# Carolo_20200123.net
KiCad netlist of a schematic drawn in EAGLE
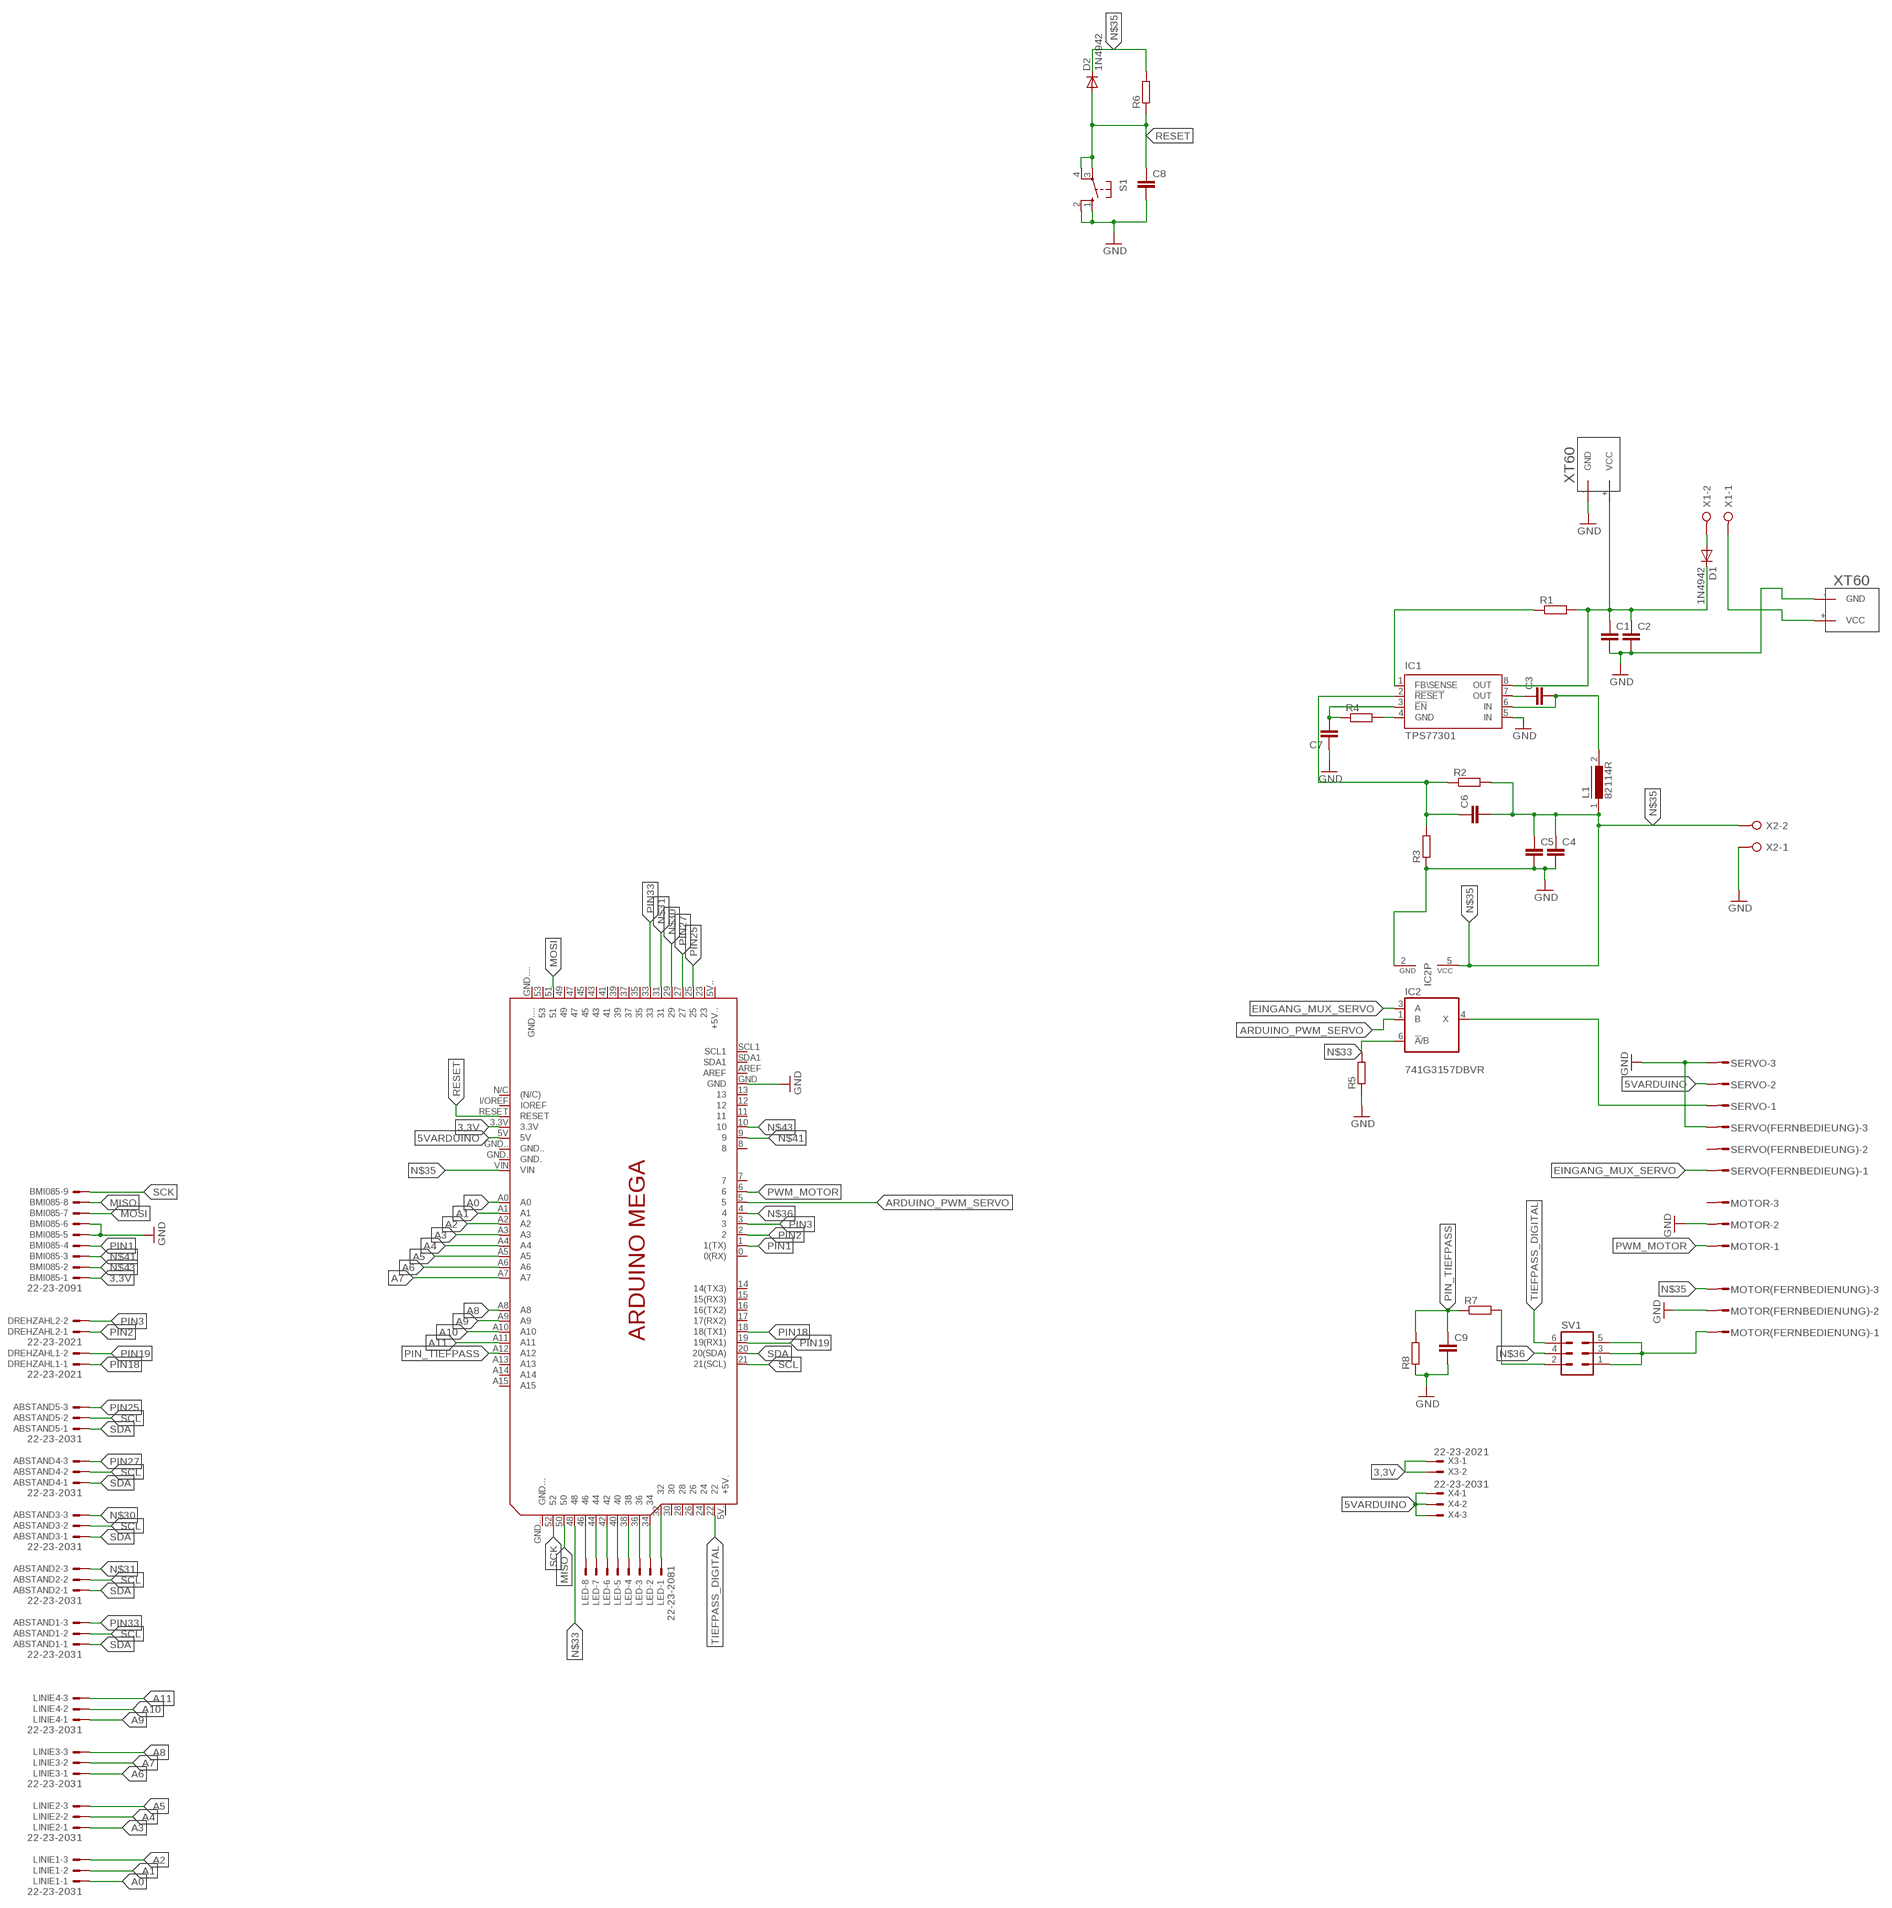
[diagram p0: schematic, sheet 1]

(export (version "E")
  (design (tool "Eeschema 10.0.6"))
  (components
    (comp (ref "ABSTAND1")
      (value "22-23-2031")
      (footprint "eagle-import:22-23-2031")
      (fields (field (name "MF") "MOLEX"))
      (libsource (lib "eagle-import") (part "22-23-2031"))
    )
    (comp (ref "ABSTAND2")
      (value "22-23-2031")
      (footprint "eagle-import:22-23-2031")
      (fields (field (name "MF") "MOLEX"))
      (libsource (lib "eagle-import") (part "22-23-2031"))
    )
    (comp (ref "ABSTAND3")
      (value "22-23-2031")
      (footprint "eagle-import:22-23-2031")
      (fields (field (name "MF") "MOLEX"))
      (libsource (lib "eagle-import") (part "22-23-2031"))
    )
    (comp (ref "ABSTAND4")
      (value "22-23-2031")
      (footprint "eagle-import:22-23-2031")
      (fields (field (name "MF") "MOLEX"))
      (libsource (lib "eagle-import") (part "22-23-2031"))
    )
    (comp (ref "ABSTAND5")
      (value "22-23-2031")
      (footprint "eagle-import:22-23-2031")
      (fields (field (name "MF") "MOLEX"))
      (libsource (lib "eagle-import") (part "22-23-2031"))
    )
    (comp (ref "BMI085")
      (value "22-23-2091")
      (footprint "eagle-import:22-23-2091")
      (fields (field (name "MF") "MOLEX"))
      (libsource (lib "eagle-import") (part "22-23-2091"))
    )
    (comp (ref "C1")
      (value "C2,5-3")
      (footprint "eagle-import:C2.5-3")
      (libsource (lib "eagle-import") (part "C2,5-3"))
    )
    (comp (ref "C2")
      (value "C2,5-3")
      (footprint "eagle-import:C2.5-3")
      (libsource (lib "eagle-import") (part "C2,5-3"))
    )
    (comp (ref "C3")
      (value "C2,5-3")
      (footprint "eagle-import:C2.5-3")
      (libsource (lib "eagle-import") (part "C2,5-3"))
    )
    (comp (ref "C4")
      (value "C2,5-3")
      (footprint "eagle-import:C2.5-3")
      (libsource (lib "eagle-import") (part "C2,5-3"))
    )
    (comp (ref "C5")
      (value "C2,5-3")
      (footprint "eagle-import:C2.5-3")
      (libsource (lib "eagle-import") (part "C2,5-3"))
    )
    (comp (ref "C6")
      (value "C2,5-3")
      (footprint "eagle-import:C2.5-3")
      (libsource (lib "eagle-import") (part "C2,5-3"))
    )
    (comp (ref "C7")
      (value "C2,5-3")
      (footprint "eagle-import:C2.5-3")
      (libsource (lib "eagle-import") (part "C2,5-3"))
    )
    (comp (ref "C8")
      (value "C2,5-3")
      (footprint "eagle-import:C2.5-3")
      (libsource (lib "eagle-import") (part "C2,5-3"))
    )
    (comp (ref "C9")
      (value "C2,5-3")
      (footprint "eagle-import:C2.5-3")
      (libsource (lib "eagle-import") (part "C2,5-3"))
    )
    (comp (ref "D1")
      (value "1N4942")
      (footprint "eagle-import:DO41-10")
      (libsource (lib "eagle-import") (part "1N4942"))
    )
    (comp (ref "D2")
      (value "1N4942")
      (footprint "eagle-import:DO41-10")
      (libsource (lib "eagle-import") (part "1N4942"))
    )
    (comp (ref "DREHZAHL1")
      (value "22-23-2021")
      (footprint "eagle-import:22-23-2021")
      (fields (field (name "MF") "MOLEX"))
      (libsource (lib "eagle-import") (part "22-23-2021"))
    )
    (comp (ref "DREHZAHL2")
      (value "22-23-2021")
      (footprint "eagle-import:22-23-2021")
      (fields (field (name "MF") "MOLEX"))
      (libsource (lib "eagle-import") (part "22-23-2021"))
    )
    (comp (ref "IC1")
      (value "TPS77301")
      (footprint "eagle-import:SOP-08")
      (fields (field (name "MF") "TEXAS INSTRUMENT CONNECTORS") (field (name "MPN") "TPS77301DGK"))
      (libsource (lib "eagle-import") (part "TPS77301"))
    )
    (comp (ref "IC2")
      (value "741G3157DBVR")
      (footprint "eagle-import:DBV_R-PDSO-G6")
      (libsource (lib "eagle-import") (part "741G3157DBVR"))
    )
    (comp (ref "L1")
      (value "82114R")
      (footprint "eagle-import:82114R")
      (libsource (lib "eagle-import") (part "82114R"))
    )
    (comp (ref "LED")
      (value "22-23-2081")
      (footprint "eagle-import:22-23-2081")
      (fields (field (name "MF") "MOLEX"))
      (libsource (lib "eagle-import") (part "22-23-2081"))
    )
    (comp (ref "LINIE1")
      (value "22-23-2031")
      (footprint "eagle-import:22-23-2031")
      (fields (field (name "MF") "MOLEX"))
      (libsource (lib "eagle-import") (part "22-23-2031"))
    )
    (comp (ref "LINIE2")
      (value "22-23-2031")
      (footprint "eagle-import:22-23-2031")
      (fields (field (name "MF") "MOLEX"))
      (libsource (lib "eagle-import") (part "22-23-2031"))
    )
    (comp (ref "LINIE3")
      (value "22-23-2031")
      (footprint "eagle-import:22-23-2031")
      (fields (field (name "MF") "MOLEX"))
      (libsource (lib "eagle-import") (part "22-23-2031"))
    )
    (comp (ref "LINIE4")
      (value "22-23-2031")
      (footprint "eagle-import:22-23-2031")
      (fields (field (name "MF") "MOLEX"))
      (libsource (lib "eagle-import") (part "22-23-2031"))
    )
    (comp (ref "MOTOR")
      (value "L03P")
      (footprint "eagle-import:L03P")
      (libsource (lib "eagle-import") (part "L03P"))
    )
    (comp (ref "MOTOR(FERNBEDIENUNG)")
      (value "L03P")
      (footprint "eagle-import:L03P")
      (libsource (lib "eagle-import") (part "L03P"))
    )
    (comp (ref "PCB1")
      (value "ARDUINO_MEGA")
      (footprint "eagle-import:ARDUINO_MEGA")
      (libsource (lib "eagle-import") (part "ARDUINO_MEGA"))
    )
    (comp (ref "R1")
      (value "R-EU_0411/15")
      (footprint "eagle-import:0411_15")
      (libsource (lib "eagle-import") (part "R-EU_0411/15"))
    )
    (comp (ref "R2")
      (value "R-EU_0411/15")
      (footprint "eagle-import:0411_15")
      (libsource (lib "eagle-import") (part "R-EU_0411/15"))
    )
    (comp (ref "R3")
      (value "R-EU_0411/15")
      (footprint "eagle-import:0411_15")
      (libsource (lib "eagle-import") (part "R-EU_0411/15"))
    )
    (comp (ref "R4")
      (value "R-EU_0411/15")
      (footprint "eagle-import:0411_15")
      (libsource (lib "eagle-import") (part "R-EU_0411/15"))
    )
    (comp (ref "R5")
      (value "R-EU_0411/15")
      (footprint "eagle-import:0411_15")
      (libsource (lib "eagle-import") (part "R-EU_0411/15"))
    )
    (comp (ref "R6")
      (value "R-EU_0411/15")
      (footprint "eagle-import:0411_15")
      (libsource (lib "eagle-import") (part "R-EU_0411/15"))
    )
    (comp (ref "R7")
      (value "R-EU_0411/15")
      (footprint "eagle-import:0411_15")
      (libsource (lib "eagle-import") (part "R-EU_0411/15"))
    )
    (comp (ref "R8")
      (value "R-EU_0411/15")
      (footprint "eagle-import:0411_15")
      (libsource (lib "eagle-import") (part "R-EU_0411/15"))
    )
    (comp (ref "S1")
      (value "10-XX")
      (footprint "eagle-import:B3F-10XX")
      (fields (field (name "MPN") "B3F-1000"))
      (libsource (lib "eagle-import") (part "10-XX"))
    )
    (comp (ref "SERVO")
      (value "L03P")
      (footprint "eagle-import:L03P")
      (libsource (lib "eagle-import") (part "L03P"))
    )
    (comp (ref "SERVO(FERNBEDIEUNG)")
      (value "L03P")
      (footprint "eagle-import:L03P")
      (libsource (lib "eagle-import") (part "L03P"))
    )
    (comp (ref "SV1")
      (value "ML6")
      (footprint "eagle-import:ML6")
      (libsource (lib "eagle-import") (part "ML6"))
    )
    (comp (ref "U$1")
      (value "XT60")
      (footprint "eagle-import:XT60")
      (libsource (lib "eagle-import") (part "XT60"))
    )
    (comp (ref "U$2")
      (value "XT60")
      (footprint "eagle-import:XT60")
      (libsource (lib "eagle-import") (part "XT60"))
    )
    (comp (ref "X1")
      (value "W237-02P")
      (footprint "eagle-import:W237-132")
      (libsource (lib "eagle-import") (part "W237-02P"))
    )
    (comp (ref "X2")
      (value "W237-02P")
      (footprint "eagle-import:W237-132")
      (libsource (lib "eagle-import") (part "W237-02P"))
    )
    (comp (ref "X3")
      (value "22-23-2021")
      (footprint "eagle-import:22-23-2021")
      (fields (field (name "MF") "MOLEX"))
      (libsource (lib "eagle-import") (part "22-23-2021"))
    )
    (comp (ref "X4")
      (value "22-23-2031")
      (footprint "eagle-import:22-23-2031")
      (fields (field (name "MF") "MOLEX"))
      (libsource (lib "eagle-import") (part "22-23-2031"))
    )
  )
  (nets
    (net (code "1") (name "3,3V") (class "Default")
      (node (ref "BMI085") (pin "1") (pinfunction "S_1") (pintype "passive"))
      (node (ref "PCB1") (pin "3.3V") (pinfunction "3.3V_3.3V") (pintype "bidirectional"))
      (node (ref "X3") (pin "1") (pinfunction "S_1") (pintype "passive"))
      (node (ref "X3") (pin "2") (pinfunction "S_2") (pintype "passive"))
    )
    (net (code "2") (name "5VARDUINO") (class "Default")
      (node (ref "PCB1") (pin "5V") (pinfunction "5V_5V") (pintype "bidirectional"))
      (node (ref "SERVO") (pin "2") (pinfunction "S_2") (pintype "passive"))
      (node (ref "X4") (pin "1") (pinfunction "S_1") (pintype "passive"))
      (node (ref "X4") (pin "2") (pinfunction "S_2") (pintype "passive"))
      (node (ref "X4") (pin "3") (pinfunction "S_3") (pintype "passive"))
    )
    (net (code "3") (name "A0") (class "Default")
      (node (ref "LINIE1") (pin "1") (pinfunction "S_1") (pintype "passive"))
      (node (ref "PCB1") (pin "A0") (pinfunction "A0_A0") (pintype "bidirectional"))
    )
    (net (code "4") (name "A1") (class "Default")
      (node (ref "LINIE1") (pin "2") (pinfunction "S_2") (pintype "passive"))
      (node (ref "PCB1") (pin "A1") (pinfunction "A1_A1") (pintype "bidirectional"))
    )
    (net (code "5") (name "A2") (class "Default")
      (node (ref "LINIE1") (pin "3") (pinfunction "S_3") (pintype "passive"))
      (node (ref "PCB1") (pin "A2") (pinfunction "A2_A2") (pintype "bidirectional"))
    )
    (net (code "6") (name "A3") (class "Default")
      (node (ref "LINIE2") (pin "1") (pinfunction "S_1") (pintype "passive"))
      (node (ref "PCB1") (pin "A3") (pinfunction "A3_A3") (pintype "bidirectional"))
    )
    (net (code "7") (name "A4") (class "Default")
      (node (ref "LINIE2") (pin "2") (pinfunction "S_2") (pintype "passive"))
      (node (ref "PCB1") (pin "A4") (pinfunction "A4_A4") (pintype "bidirectional"))
    )
    (net (code "8") (name "A5") (class "Default")
      (node (ref "LINIE2") (pin "3") (pinfunction "S_3") (pintype "passive"))
      (node (ref "PCB1") (pin "A5") (pinfunction "A5_A5") (pintype "bidirectional"))
    )
    (net (code "9") (name "A6") (class "Default")
      (node (ref "LINIE3") (pin "1") (pinfunction "S_1") (pintype "passive"))
      (node (ref "PCB1") (pin "A6") (pinfunction "A6_A6") (pintype "bidirectional"))
    )
    (net (code "10") (name "A7") (class "Default")
      (node (ref "LINIE3") (pin "2") (pinfunction "S_2") (pintype "passive"))
      (node (ref "PCB1") (pin "A7") (pinfunction "A7_A7") (pintype "bidirectional"))
    )
    (net (code "11") (name "A8") (class "Default")
      (node (ref "LINIE3") (pin "3") (pinfunction "S_3") (pintype "passive"))
      (node (ref "PCB1") (pin "A8") (pinfunction "A8_A8") (pintype "bidirectional"))
    )
    (net (code "12") (name "A9") (class "Default")
      (node (ref "LINIE4") (pin "1") (pinfunction "S_1") (pintype "passive"))
      (node (ref "PCB1") (pin "A9") (pinfunction "A9_A9") (pintype "bidirectional"))
    )
    (net (code "13") (name "A10") (class "Default")
      (node (ref "LINIE4") (pin "2") (pinfunction "S_2") (pintype "passive"))
      (node (ref "PCB1") (pin "A10") (pinfunction "A10_A10") (pintype "bidirectional"))
    )
    (net (code "14") (name "A11") (class "Default")
      (node (ref "LINIE4") (pin "3") (pinfunction "S_3") (pintype "passive"))
      (node (ref "PCB1") (pin "A11") (pinfunction "A11_A11") (pintype "bidirectional"))
    )
    (net (code "15") (name "ARDUINO_PWM_SERVO") (class "Default")
      (node (ref "IC2") (pin "1") (pinfunction "B_1") (pintype "bidirectional"))
      (node (ref "PCB1") (pin "5") (pinfunction "5_5") (pintype "bidirectional"))
    )
    (net (code "16") (name "EINGANG_MUX_SERVO") (class "Default")
      (node (ref "IC2") (pin "3") (pinfunction "A_3") (pintype "bidirectional"))
      (node (ref "SERVO(FERNBEDIEUNG)") (pin "1") (pinfunction "S_1") (pintype "passive"))
    )
    (net (code "17") (name "GND") (class "Default")
      (node (ref "BMI085") (pin "5") (pinfunction "S_5") (pintype "passive"))
      (node (ref "BMI085") (pin "6") (pinfunction "S_6") (pintype "passive"))
      (node (ref "C1") (pin "2") (pinfunction "2_2") (pintype "passive"))
      (node (ref "C2") (pin "2") (pinfunction "2_2") (pintype "passive"))
      (node (ref "C4") (pin "2") (pinfunction "2_2") (pintype "passive"))
      (node (ref "C5") (pin "2") (pinfunction "2_2") (pintype "passive"))
      (node (ref "C7") (pin "1") (pinfunction "1_1") (pintype "passive"))
      (node (ref "C8") (pin "2") (pinfunction "2_2") (pintype "passive"))
      (node (ref "C9") (pin "2") (pinfunction "2_2") (pintype "passive"))
      (node (ref "IC1") (pin "5") (pinfunction "IN_5") (pintype "input"))
      (node (ref "IC2") (pin "2") (pinfunction "GND_2") (pintype "power_in"))
      (node (ref "MOTOR") (pin "2") (pinfunction "S_2") (pintype "passive"))
      (node (ref "MOTOR(FERNBEDIENUNG)") (pin "2") (pinfunction "S_2") (pintype "passive"))
      (node (ref "PCB1") (pin "GND") (pinfunction "GND_GND") (pintype "bidirectional"))
      (node (ref "R3") (pin "1") (pinfunction "1_1") (pintype "passive"))
      (node (ref "R5") (pin "1") (pinfunction "1_1") (pintype "passive"))
      (node (ref "R8") (pin "1") (pinfunction "1_1") (pintype "passive"))
      (node (ref "S1") (pin "1") (pinfunction "S_1") (pintype "passive"))
      (node (ref "S1") (pin "2") (pinfunction "S1_2") (pintype "passive"))
      (node (ref "SERVO") (pin "3") (pinfunction "S_3") (pintype "passive"))
      (node (ref "SERVO(FERNBEDIEUNG)") (pin "3") (pinfunction "S_3") (pintype "passive"))
      (node (ref "U$1") (pin "-") (pinfunction "GND_-") (pintype "bidirectional"))
      (node (ref "U$2") (pin "-") (pinfunction "GND_-") (pintype "bidirectional"))
      (node (ref "X2") (pin "1") (pinfunction "KL_1") (pintype "passive"))
    )
    (net (code "18") (name "MISO") (class "Default")
      (node (ref "BMI085") (pin "8") (pinfunction "S_8") (pintype "passive"))
      (node (ref "PCB1") (pin "50") (pinfunction "50_50") (pintype "bidirectional"))
    )
    (net (code "19") (name "MOSI") (class "Default")
      (node (ref "BMI085") (pin "7") (pinfunction "S_7") (pintype "passive"))
      (node (ref "PCB1") (pin "51") (pinfunction "51_51") (pintype "bidirectional"))
    )
    (net (code "20") (name "N$30") (class "Default")
      (node (ref "ABSTAND3") (pin "3") (pinfunction "S_3") (pintype "passive"))
      (node (ref "PCB1") (pin "29") (pinfunction "29_29") (pintype "bidirectional"))
    )
    (net (code "21") (name "N$31") (class "Default")
      (node (ref "ABSTAND2") (pin "3") (pinfunction "S_3") (pintype "passive"))
      (node (ref "PCB1") (pin "31") (pinfunction "31_31") (pintype "bidirectional"))
    )
    (net (code "22") (name "N$33") (class "Default")
      (node (ref "IC2") (pin "6") (pinfunction "~{A}/B_6") (pintype "input"))
      (node (ref "PCB1") (pin "48") (pinfunction "48_48") (pintype "bidirectional"))
      (node (ref "R5") (pin "2") (pinfunction "2_2") (pintype "passive"))
    )
    (net (code "23") (name "N$35") (class "Default")
      (node (ref "C4") (pin "1") (pinfunction "1_1") (pintype "passive"))
      (node (ref "C5") (pin "1") (pinfunction "1_1") (pintype "passive"))
      (node (ref "C6") (pin "2") (pinfunction "2_2") (pintype "passive"))
      (node (ref "D2") (pin "C") (pinfunction "C_C") (pintype "passive"))
      (node (ref "IC2") (pin "5") (pinfunction "VCC_5") (pintype "power_in"))
      (node (ref "L1") (pin "1") (pinfunction "1_1") (pintype "passive"))
      (node (ref "MOTOR(FERNBEDIENUNG)") (pin "3") (pinfunction "S_3") (pintype "passive"))
      (node (ref "PCB1") (pin "VIN") (pinfunction "VIN_VIN") (pintype "bidirectional"))
      (node (ref "R2") (pin "2") (pinfunction "2_2") (pintype "passive"))
      (node (ref "R6") (pin "2") (pinfunction "2_2") (pintype "passive"))
      (node (ref "X2") (pin "2") (pinfunction "KL_2") (pintype "passive"))
    )
    (net (code "24") (name "N$36") (class "Default")
      (node (ref "PCB1") (pin "4") (pinfunction "4_4") (pintype "bidirectional"))
      (node (ref "SV1") (pin "4") (pinfunction "4_4") (pintype "passive"))
    )
    (net (code "25") (name "N$41") (class "Default")
      (node (ref "BMI085") (pin "3") (pinfunction "S_3") (pintype "passive"))
      (node (ref "PCB1") (pin "9") (pinfunction "9_9") (pintype "bidirectional"))
    )
    (net (code "26") (name "N$43") (class "Default")
      (node (ref "BMI085") (pin "2") (pinfunction "S_2") (pintype "passive"))
      (node (ref "PCB1") (pin "10") (pinfunction "10_10") (pintype "bidirectional"))
    )
    (net (code "27") (name "Net-(C3-Pad1)") (class "Default")
      (node (ref "C3") (pin "1") (pinfunction "1_1") (pintype "passive"))
      (node (ref "IC1") (pin "7") (pinfunction "OUT_7") (pintype "output"))
    )
    (net (code "28") (name "Net-(C3-Pad2)") (class "Default")
      (node (ref "C3") (pin "2") (pinfunction "2_2") (pintype "passive"))
      (node (ref "IC1") (pin "6") (pinfunction "IN_6") (pintype "input"))
      (node (ref "L1") (pin "2") (pinfunction "2_2") (pintype "passive"))
    )
    (net (code "29") (name "Net-(IC1-FB\\SENSE)") (class "Default")
      (node (ref "IC1") (pin "1") (pinfunction "FB\\SENSE_1") (pintype "input"))
      (node (ref "R1") (pin "1") (pinfunction "1_1") (pintype "passive"))
    )
    (net (code "30") (name "Net-(IC1-GND)") (class "Default")
      (node (ref "IC1") (pin "4") (pinfunction "GND_4") (pintype "power_in"))
      (node (ref "R4") (pin "2") (pinfunction "2_2") (pintype "passive"))
    )
    (net (code "31") (name "Net-(IC1-~{EN})") (class "Default")
      (node (ref "C7") (pin "2") (pinfunction "2_2") (pintype "passive"))
      (node (ref "IC1") (pin "3") (pinfunction "~{EN}_3") (pintype "input"))
      (node (ref "R4") (pin "1") (pinfunction "1_1") (pintype "passive"))
    )
    (net (code "32") (name "Net-(IC1-~{RESET})") (class "Default")
      (node (ref "C6") (pin "1") (pinfunction "1_1") (pintype "passive"))
      (node (ref "IC1") (pin "2") (pinfunction "~{RESET}_2") (pintype "input"))
      (node (ref "R2") (pin "1") (pinfunction "1_1") (pintype "passive"))
      (node (ref "R3") (pin "2") (pinfunction "2_2") (pintype "passive"))
    )
    (net (code "33") (name "Net-(IC2A-X)") (class "Default")
      (node (ref "IC2") (pin "4") (pinfunction "X_4") (pintype "bidirectional"))
      (node (ref "SERVO") (pin "1") (pinfunction "S_1") (pintype "passive"))
    )
    (net (code "34") (name "Net-(LEDA-S)") (class "Default")
      (node (ref "LED") (pin "1") (pinfunction "S_1") (pintype "passive"))
      (node (ref "PCB1") (pin "32") (pinfunction "32_32") (pintype "bidirectional"))
    )
    (net (code "35") (name "Net-(LEDB-S)") (class "Default")
      (node (ref "LED") (pin "2") (pinfunction "S_2") (pintype "passive"))
      (node (ref "PCB1") (pin "34") (pinfunction "34_34") (pintype "bidirectional"))
    )
    (net (code "36") (name "Net-(LEDC-S)") (class "Default")
      (node (ref "LED") (pin "3") (pinfunction "S_3") (pintype "passive"))
      (node (ref "PCB1") (pin "36") (pinfunction "36_36") (pintype "bidirectional"))
    )
    (net (code "37") (name "Net-(LEDD-S)") (class "Default")
      (node (ref "LED") (pin "4") (pinfunction "S_4") (pintype "passive"))
      (node (ref "PCB1") (pin "38") (pinfunction "38_38") (pintype "bidirectional"))
    )
    (net (code "38") (name "Net-(LEDE-S)") (class "Default")
      (node (ref "LED") (pin "5") (pinfunction "S_5") (pintype "passive"))
      (node (ref "PCB1") (pin "40") (pinfunction "40_40") (pintype "bidirectional"))
    )
    (net (code "39") (name "Net-(LEDF-S)") (class "Default")
      (node (ref "LED") (pin "6") (pinfunction "S_6") (pintype "passive"))
      (node (ref "PCB1") (pin "42") (pinfunction "42_42") (pintype "bidirectional"))
    )
    (net (code "40") (name "Net-(LEDG-S)") (class "Default")
      (node (ref "LED") (pin "7") (pinfunction "S_7") (pintype "passive"))
      (node (ref "PCB1") (pin "44") (pinfunction "44_44") (pintype "bidirectional"))
    )
    (net (code "41") (name "Net-(LEDH-S)") (class "Default")
      (node (ref "LED") (pin "8") (pinfunction "S_8") (pintype "passive"))
      (node (ref "PCB1") (pin "46") (pinfunction "46_46") (pintype "bidirectional"))
    )
    (net (code "42") (name "Net-(MOTOR(FERNBEDIENUNG)A-S)") (class "Default")
      (node (ref "MOTOR(FERNBEDIENUNG)") (pin "1") (pinfunction "S_1") (pintype "passive"))
      (node (ref "SV1") (pin "1") (pinfunction "1_1") (pintype "passive"))
      (node (ref "SV1") (pin "3") (pinfunction "3_3") (pintype "passive"))
      (node (ref "SV1") (pin "5") (pinfunction "5_5") (pintype "passive"))
    )
    (net (code "43") (name "Net-(R7-Pad2)") (class "Default")
      (node (ref "R7") (pin "2") (pinfunction "2_2") (pintype "passive"))
      (node (ref "SV1") (pin "2") (pinfunction "2_2") (pintype "passive"))
    )
    (net (code "44") (name "Net-(U$1-VCC)") (class "Default")
      (node (ref "U$1") (pin "+") (pinfunction "VCC_+") (pintype "bidirectional"))
      (node (ref "X1") (pin "1") (pinfunction "KL_1") (pintype "passive"))
    )
    (net (code "45") (name "Net-(U$2-VCC)") (class "Default")
      (node (ref "C1") (pin "1") (pinfunction "1_1") (pintype "passive"))
      (node (ref "C2") (pin "1") (pinfunction "1_1") (pintype "passive"))
      (node (ref "D1") (pin "C") (pinfunction "C_C") (pintype "passive"))
      (node (ref "IC1") (pin "8") (pinfunction "OUT_8") (pintype "passive"))
      (node (ref "R1") (pin "2") (pinfunction "2_2") (pintype "passive"))
      (node (ref "U$2") (pin "+") (pinfunction "VCC_+") (pintype "bidirectional"))
    )
    (net (code "46") (name "Net-(X1B-KL)") (class "Default")
      (node (ref "D1") (pin "A") (pinfunction "A_A") (pintype "passive"))
      (node (ref "X1") (pin "2") (pinfunction "KL_2") (pintype "passive"))
    )
    (net (code "47") (name "PIN1") (class "Default")
      (node (ref "BMI085") (pin "4") (pinfunction "S_4") (pintype "passive"))
      (node (ref "PCB1") (pin "1") (pinfunction "1(TX)_1") (pintype "bidirectional"))
    )
    (net (code "48") (name "PIN2") (class "Default")
      (node (ref "DREHZAHL2") (pin "1") (pinfunction "S_1") (pintype "passive"))
      (node (ref "PCB1") (pin "2") (pinfunction "2_2") (pintype "bidirectional"))
    )
    (net (code "49") (name "PIN3") (class "Default")
      (node (ref "DREHZAHL2") (pin "2") (pinfunction "S_2") (pintype "passive"))
      (node (ref "PCB1") (pin "3") (pinfunction "3_3") (pintype "bidirectional"))
    )
    (net (code "50") (name "PIN18") (class "Default")
      (node (ref "DREHZAHL1") (pin "1") (pinfunction "S_1") (pintype "passive"))
      (node (ref "PCB1") (pin "18") (pinfunction "18(TX1)_18") (pintype "bidirectional"))
    )
    (net (code "51") (name "PIN19") (class "Default")
      (node (ref "DREHZAHL1") (pin "2") (pinfunction "S_2") (pintype "passive"))
      (node (ref "PCB1") (pin "19") (pinfunction "19(RX1)_19") (pintype "bidirectional"))
    )
    (net (code "52") (name "PIN25") (class "Default")
      (node (ref "ABSTAND5") (pin "3") (pinfunction "S_3") (pintype "passive"))
      (node (ref "PCB1") (pin "25") (pinfunction "25_25") (pintype "bidirectional"))
    )
    (net (code "53") (name "PIN27") (class "Default")
      (node (ref "ABSTAND4") (pin "3") (pinfunction "S_3") (pintype "passive"))
      (node (ref "PCB1") (pin "27") (pinfunction "27_27") (pintype "bidirectional"))
    )
    (net (code "54") (name "PIN33") (class "Default")
      (node (ref "ABSTAND1") (pin "3") (pinfunction "S_3") (pintype "passive"))
      (node (ref "PCB1") (pin "33") (pinfunction "33_33") (pintype "bidirectional"))
    )
    (net (code "55") (name "PIN_TIEFPASS") (class "Default")
      (node (ref "C9") (pin "1") (pinfunction "1_1") (pintype "passive"))
      (node (ref "PCB1") (pin "A12") (pinfunction "A12_A12") (pintype "bidirectional"))
      (node (ref "R7") (pin "1") (pinfunction "1_1") (pintype "passive"))
      (node (ref "R8") (pin "2") (pinfunction "2_2") (pintype "passive"))
    )
    (net (code "56") (name "PWM_MOTOR") (class "Default")
      (node (ref "MOTOR") (pin "1") (pinfunction "S_1") (pintype "passive"))
      (node (ref "PCB1") (pin "6") (pinfunction "6_6") (pintype "bidirectional"))
    )
    (net (code "57") (name "RESET") (class "Default")
      (node (ref "C8") (pin "1") (pinfunction "1_1") (pintype "passive"))
      (node (ref "D2") (pin "A") (pinfunction "A_A") (pintype "passive"))
      (node (ref "PCB1") (pin "RESET") (pinfunction "RESET_RESET") (pintype "bidirectional"))
      (node (ref "R6") (pin "1") (pinfunction "1_1") (pintype "passive"))
      (node (ref "S1") (pin "3") (pinfunction "P_3") (pintype "passive"))
      (node (ref "S1") (pin "4") (pinfunction "P1_4") (pintype "passive"))
    )
    (net (code "58") (name "SCK") (class "Default")
      (node (ref "BMI085") (pin "9") (pinfunction "S_9") (pintype "passive"))
      (node (ref "PCB1") (pin "52") (pinfunction "52_52") (pintype "bidirectional"))
    )
    (net (code "59") (name "SCL") (class "Default")
      (node (ref "ABSTAND1") (pin "2") (pinfunction "S_2") (pintype "passive"))
      (node (ref "ABSTAND2") (pin "2") (pinfunction "S_2") (pintype "passive"))
      (node (ref "ABSTAND3") (pin "2") (pinfunction "S_2") (pintype "passive"))
      (node (ref "ABSTAND4") (pin "2") (pinfunction "S_2") (pintype "passive"))
      (node (ref "ABSTAND5") (pin "2") (pinfunction "S_2") (pintype "passive"))
      (node (ref "PCB1") (pin "21") (pinfunction "21(SCL)_21") (pintype "bidirectional"))
    )
    (net (code "60") (name "SDA") (class "Default")
      (node (ref "ABSTAND1") (pin "1") (pinfunction "S_1") (pintype "passive"))
      (node (ref "ABSTAND2") (pin "1") (pinfunction "S_1") (pintype "passive"))
      (node (ref "ABSTAND3") (pin "1") (pinfunction "S_1") (pintype "passive"))
      (node (ref "ABSTAND4") (pin "1") (pinfunction "S_1") (pintype "passive"))
      (node (ref "ABSTAND5") (pin "1") (pinfunction "S_1") (pintype "passive"))
      (node (ref "PCB1") (pin "20") (pinfunction "20(SDA)_20") (pintype "bidirectional"))
    )
    (net (code "61") (name "TIEFPASS_DIGITAL") (class "Default")
      (node (ref "PCB1") (pin "22") (pinfunction "22_22") (pintype "bidirectional"))
      (node (ref "SV1") (pin "6") (pinfunction "6_6") (pintype "passive"))
    )
    (net (code "62") (name "unconnected-(MOTORC-S-Pad3)") (class "Default")
      (node (ref "MOTOR") (pin "3") (pinfunction "S_3") (pintype "passive"))
    )
    (net (code "63") (name "unconnected-(PCB1-(N{slash}C)-PadN{slash}C)") (class "Default")
      (node (ref "PCB1") (pin "N/C") (pinfunction "(N/C)_N/C") (pintype "bidirectional"))
    )
    (net (code "64") (name "unconnected-(PCB1-+5V.-Pad5V.)") (class "Default")
      (node (ref "PCB1") (pin "5V.") (pinfunction "+5V._5V.") (pintype "bidirectional"))
    )
    (net (code "65") (name "unconnected-(PCB1-+5V..-Pad5V..)") (class "Default")
      (node (ref "PCB1") (pin "5V..") (pinfunction "+5V.._5V..") (pintype "bidirectional"))
    )
    (net (code "66") (name "unconnected-(PCB1-0(RX)-Pad0)") (class "Default")
      (node (ref "PCB1") (pin "0") (pinfunction "0(RX)_0") (pintype "bidirectional"))
    )
    (net (code "67") (name "unconnected-(PCB1-14(TX3)-Pad14)") (class "Default")
      (node (ref "PCB1") (pin "14") (pinfunction "14(TX3)_14") (pintype "bidirectional"))
    )
    (net (code "68") (name "unconnected-(PCB1-15(RX3)-Pad15)") (class "Default")
      (node (ref "PCB1") (pin "15") (pinfunction "15(RX3)_15") (pintype "bidirectional"))
    )
    (net (code "69") (name "unconnected-(PCB1-16(TX2)-Pad16)") (class "Default")
      (node (ref "PCB1") (pin "16") (pinfunction "16(TX2)_16") (pintype "bidirectional"))
    )
    (net (code "70") (name "unconnected-(PCB1-17(RX2)-Pad17)") (class "Default")
      (node (ref "PCB1") (pin "17") (pinfunction "17(RX2)_17") (pintype "bidirectional"))
    )
    (net (code "71") (name "unconnected-(PCB1-IOREF-PadI{slash}OREF)") (class "Default")
      (node (ref "PCB1") (pin "I/OREF") (pinfunction "IOREF_I/OREF") (pintype "bidirectional"))
    )
    (net (code "72") (name "unconnected-(PCB1-Pad7)") (class "Default")
      (node (ref "PCB1") (pin "7") (pinfunction "7_7") (pintype "bidirectional"))
    )
    (net (code "73") (name "unconnected-(PCB1-Pad8)") (class "Default")
      (node (ref "PCB1") (pin "8") (pinfunction "8_8") (pintype "bidirectional"))
    )
    (net (code "74") (name "unconnected-(PCB1-Pad11)") (class "Default")
      (node (ref "PCB1") (pin "11") (pinfunction "11_11") (pintype "bidirectional"))
    )
    (net (code "75") (name "unconnected-(PCB1-Pad12)") (class "Default")
      (node (ref "PCB1") (pin "12") (pinfunction "12_12") (pintype "bidirectional"))
    )
    (net (code "76") (name "unconnected-(PCB1-Pad13)") (class "Default")
      (node (ref "PCB1") (pin "13") (pinfunction "13_13") (pintype "bidirectional"))
    )
    (net (code "77") (name "unconnected-(PCB1-Pad23)") (class "Default")
      (node (ref "PCB1") (pin "23") (pinfunction "23_23") (pintype "bidirectional"))
    )
    (net (code "78") (name "unconnected-(PCB1-Pad24)") (class "Default")
      (node (ref "PCB1") (pin "24") (pinfunction "24_24") (pintype "bidirectional"))
    )
    (net (code "79") (name "unconnected-(PCB1-Pad26)") (class "Default")
      (node (ref "PCB1") (pin "26") (pinfunction "26_26") (pintype "bidirectional"))
    )
    (net (code "80") (name "unconnected-(PCB1-Pad28)") (class "Default")
      (node (ref "PCB1") (pin "28") (pinfunction "28_28") (pintype "bidirectional"))
    )
    (net (code "81") (name "unconnected-(PCB1-Pad30)") (class "Default")
      (node (ref "PCB1") (pin "30") (pinfunction "30_30") (pintype "bidirectional"))
    )
    (net (code "82") (name "unconnected-(PCB1-Pad35)") (class "Default")
      (node (ref "PCB1") (pin "35") (pinfunction "35_35") (pintype "bidirectional"))
    )
    (net (code "83") (name "unconnected-(PCB1-Pad37)") (class "Default")
      (node (ref "PCB1") (pin "37") (pinfunction "37_37") (pintype "bidirectional"))
    )
    (net (code "84") (name "unconnected-(PCB1-Pad39)") (class "Default")
      (node (ref "PCB1") (pin "39") (pinfunction "39_39") (pintype "bidirectional"))
    )
    (net (code "85") (name "unconnected-(PCB1-Pad41)") (class "Default")
      (node (ref "PCB1") (pin "41") (pinfunction "41_41") (pintype "bidirectional"))
    )
    (net (code "86") (name "unconnected-(PCB1-Pad43)") (class "Default")
      (node (ref "PCB1") (pin "43") (pinfunction "43_43") (pintype "bidirectional"))
    )
    (net (code "87") (name "unconnected-(PCB1-Pad45)") (class "Default")
      (node (ref "PCB1") (pin "45") (pinfunction "45_45") (pintype "bidirectional"))
    )
    (net (code "88") (name "unconnected-(PCB1-Pad47)") (class "Default")
      (node (ref "PCB1") (pin "47") (pinfunction "47_47") (pintype "bidirectional"))
    )
    (net (code "89") (name "unconnected-(PCB1-Pad49)") (class "Default")
      (node (ref "PCB1") (pin "49") (pinfunction "49_49") (pintype "bidirectional"))
    )
    (net (code "90") (name "unconnected-(PCB1-Pad53)") (class "Default")
      (node (ref "PCB1") (pin "53") (pinfunction "53_53") (pintype "bidirectional"))
    )
    (net (code "91") (name "unconnected-(PCB1-PadA13)") (class "Default")
      (node (ref "PCB1") (pin "A13") (pinfunction "A13_A13") (pintype "bidirectional"))
    )
    (net (code "92") (name "unconnected-(PCB1-PadA14)") (class "Default")
      (node (ref "PCB1") (pin "A14") (pinfunction "A14_A14") (pintype "bidirectional"))
    )
    (net (code "93") (name "unconnected-(PCB1-PadA15)") (class "Default")
      (node (ref "PCB1") (pin "A15") (pinfunction "A15_A15") (pintype "bidirectional"))
    )
    (net (code "94") (name "unconnected-(PCB1-PadAREF)") (class "Default")
      (node (ref "PCB1") (pin "AREF") (pinfunction "AREF_AREF") (pintype "bidirectional"))
    )
    (net (code "95") (name "unconnected-(PCB1-PadGND.)") (class "Default")
      (node (ref "PCB1") (pin "GND.") (pinfunction "GND._GND.") (pintype "bidirectional"))
    )
    (net (code "96") (name "unconnected-(PCB1-PadGND..)") (class "Default")
      (node (ref "PCB1") (pin "GND..") (pinfunction "GND.._GND..") (pintype "bidirectional"))
    )
    (net (code "97") (name "unconnected-(PCB1-PadGND...)") (class "Default")
      (node (ref "PCB1") (pin "GND...") (pinfunction "GND..._GND...") (pintype "bidirectional"))
    )
    (net (code "98") (name "unconnected-(PCB1-PadGND....)") (class "Default")
      (node (ref "PCB1") (pin "GND....") (pinfunction "GND...._GND....") (pintype "bidirectional"))
    )
    (net (code "99") (name "unconnected-(PCB1-PadSCL1)") (class "Default")
      (node (ref "PCB1") (pin "SCL1") (pinfunction "SCL1_SCL1") (pintype "bidirectional"))
    )
    (net (code "100") (name "unconnected-(PCB1-PadSDA1)") (class "Default")
      (node (ref "PCB1") (pin "SDA1") (pinfunction "SDA1_SDA1") (pintype "bidirectional"))
    )
    (net (code "101") (name "unconnected-(SERVO(FERNBEDIEUNG)B-S-Pad2)") (class "Default")
      (node (ref "SERVO(FERNBEDIEUNG)") (pin "2") (pinfunction "S_2") (pintype "passive"))
    )
  )
)
